# tic_tac_toe.net
KiCad netlist of a schematic drawn in EAGLE
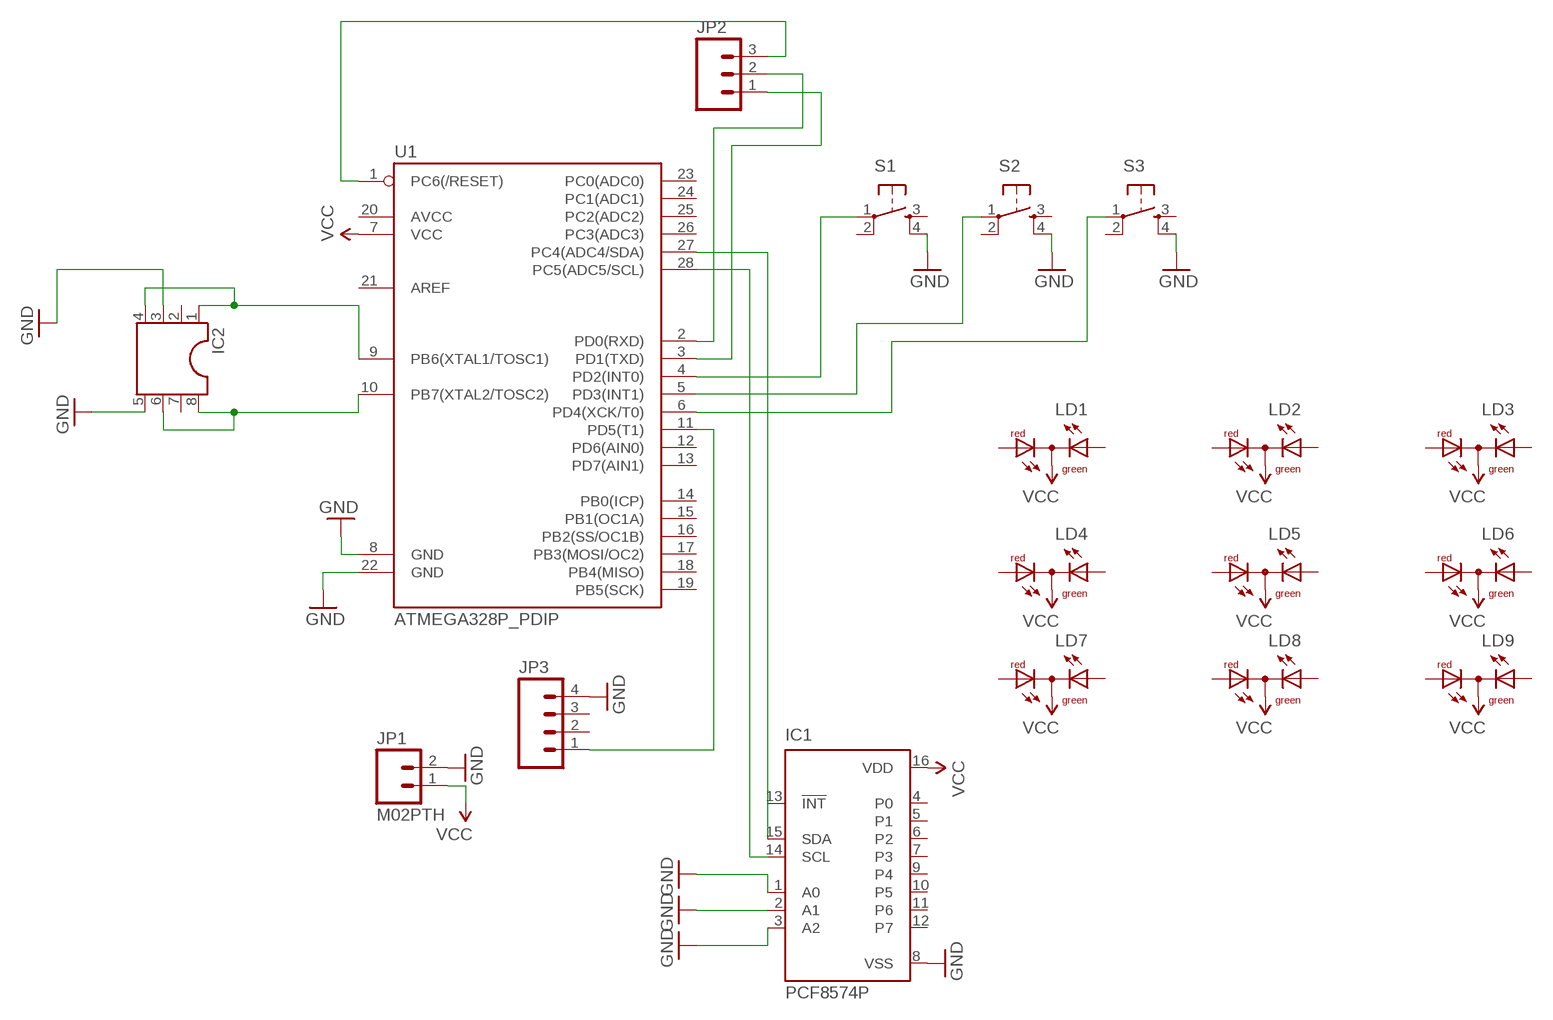
[diagram p0: schematic, sheet 1]

(export (version "E")
  (design (tool "Eeschema 10.0.6"))
  (components
    (comp (ref "IC1")
      (value "PCF8574P")
      (footprint "eagle-import:DIL16")
      (fields (field (name "MPN") "PCF8574PN"))
      (libsource (lib "eagle-import") (part "PCF8574P"))
    )
    (comp (ref "IC2")
      (value "DIL8S")
      (footprint "eagle-import:SOCKET-08")
      (libsource (lib "eagle-import") (part "DIL8S"))
    )
    (comp (ref "JP1")
      (value "M02PTH")
      (footprint "eagle-import:1X02")
      (libsource (lib "eagle-import") (part "M02PTH"))
    )
    (comp (ref "JP2")
      (value "M03PTH")
      (footprint "eagle-import:1X03")
      (libsource (lib "eagle-import") (part "M03PTH"))
    )
    (comp (ref "JP3")
      (value "M04PTH")
      (footprint "eagle-import:1X04")
      (libsource (lib "eagle-import") (part "M04PTH"))
    )
    (comp (ref "LD1")
      (value "DUOLED-RG-C")
      (footprint "eagle-import:DUOLED-C-5MM")
      (libsource (lib "eagle-import") (part "DUOLED-RG-C"))
    )
    (comp (ref "LD2")
      (value "DUOLED-RG-C")
      (footprint "eagle-import:DUOLED-C-5MM")
      (libsource (lib "eagle-import") (part "DUOLED-RG-C"))
    )
    (comp (ref "LD3")
      (value "DUOLED-RG-C")
      (footprint "eagle-import:DUOLED-C-5MM")
      (libsource (lib "eagle-import") (part "DUOLED-RG-C"))
    )
    (comp (ref "LD4")
      (value "DUOLED-RG-C")
      (footprint "eagle-import:DUOLED-C-5MM")
      (libsource (lib "eagle-import") (part "DUOLED-RG-C"))
    )
    (comp (ref "LD5")
      (value "DUOLED-RG-C")
      (footprint "eagle-import:DUOLED-C-5MM")
      (libsource (lib "eagle-import") (part "DUOLED-RG-C"))
    )
    (comp (ref "LD6")
      (value "DUOLED-RG-C")
      (footprint "eagle-import:DUOLED-C-5MM")
      (libsource (lib "eagle-import") (part "DUOLED-RG-C"))
    )
    (comp (ref "LD7")
      (value "DUOLED-RG-C")
      (footprint "eagle-import:DUOLED-C-5MM")
      (libsource (lib "eagle-import") (part "DUOLED-RG-C"))
    )
    (comp (ref "LD8")
      (value "DUOLED-RG-C")
      (footprint "eagle-import:DUOLED-C-5MM")
      (libsource (lib "eagle-import") (part "DUOLED-RG-C"))
    )
    (comp (ref "LD9")
      (value "DUOLED-RG-C")
      (footprint "eagle-import:DUOLED-C-5MM")
      (libsource (lib "eagle-import") (part "DUOLED-RG-C"))
    )
    (comp (ref "S1")
      (value "TAC_SWITCHPTH")
      (footprint "eagle-import:TACTILE-PTH")
      (libsource (lib "eagle-import") (part "TAC_SWITCHPTH"))
    )
    (comp (ref "S2")
      (value "TAC_SWITCHPTH")
      (footprint "eagle-import:TACTILE-PTH")
      (libsource (lib "eagle-import") (part "TAC_SWITCHPTH"))
    )
    (comp (ref "S3")
      (value "TAC_SWITCHPTH")
      (footprint "eagle-import:TACTILE-PTH")
      (libsource (lib "eagle-import") (part "TAC_SWITCHPTH"))
    )
    (comp (ref "U1")
      (value "ATMEGA328P_PDIP")
      (footprint "eagle-import:DIL28-3")
      (libsource (lib "eagle-import") (part "ATMEGA328P_PDIP"))
    )
  )
  (nets
    (net (code "1") (name "GND") (class "Default")
      (node (ref "IC1") (pin "1") (pinfunction "A0_1") (pintype "input"))
      (node (ref "IC1") (pin "2") (pinfunction "A1_2") (pintype "input"))
      (node (ref "IC1") (pin "3") (pinfunction "A2_3") (pintype "input"))
      (node (ref "IC1") (pin "8") (pinfunction "VSS_8") (pintype "power_in"))
      (node (ref "IC2") (pin "3") (pinfunction "3_3") (pintype "passive"))
      (node (ref "IC2") (pin "5") (pinfunction "5_5") (pintype "passive"))
      (node (ref "JP1") (pin "2") (pinfunction "2_2") (pintype "passive"))
      (node (ref "JP3") (pin "4") (pinfunction "4_4") (pintype "passive"))
      (node (ref "S1") (pin "4") (pinfunction "4_4") (pintype "passive"))
      (node (ref "S2") (pin "4") (pinfunction "4_4") (pintype "passive"))
      (node (ref "S3") (pin "4") (pinfunction "4_4") (pintype "passive"))
      (node (ref "U1") (pin "22") (pinfunction "GND_22") (pintype "bidirectional"))
      (node (ref "U1") (pin "8") (pinfunction "GND_8") (pintype "bidirectional"))
    )
    (net (code "2") (name "Net-(IC1-SCL)") (class "Default")
      (node (ref "IC1") (pin "14") (pinfunction "SCL_14") (pintype "input"))
      (node (ref "U1") (pin "28") (pinfunction "PC5(ADC5/SCL)_28") (pintype "bidirectional"))
    )
    (net (code "3") (name "Net-(IC1-SDA)") (class "Default")
      (node (ref "IC1") (pin "15") (pinfunction "SDA_15") (pintype "bidirectional"))
      (node (ref "U1") (pin "27") (pinfunction "PC4(ADC4/SDA)_27") (pintype "bidirectional"))
    )
    (net (code "4") (name "Net-(U1-PB6(XTAL1{slash}TOSC1))") (class "Default")
      (node (ref "IC2") (pin "1") (pinfunction "1_1") (pintype "passive"))
      (node (ref "IC2") (pin "4") (pinfunction "4_4") (pintype "passive"))
      (node (ref "U1") (pin "9") (pinfunction "PB6(XTAL1/TOSC1)_9") (pintype "bidirectional"))
    )
    (net (code "5") (name "Net-(U1-PB7(XTAL2{slash}TOSC2))") (class "Default")
      (node (ref "IC2") (pin "6") (pinfunction "6_6") (pintype "passive"))
      (node (ref "IC2") (pin "8") (pinfunction "8_8") (pintype "passive"))
      (node (ref "U1") (pin "10") (pinfunction "PB7(XTAL2/TOSC2)_10") (pintype "bidirectional"))
    )
    (net (code "6") (name "Net-(U1-PC6({slash}RESET))") (class "Default")
      (node (ref "JP2") (pin "3") (pinfunction "3_3") (pintype "passive"))
      (node (ref "U1") (pin "1") (pinfunction "PC6(/RESET)_1") (pintype "bidirectional"))
    )
    (net (code "7") (name "Net-(U1-PD0(RXD))") (class "Default")
      (node (ref "JP2") (pin "2") (pinfunction "2_2") (pintype "passive"))
      (node (ref "U1") (pin "2") (pinfunction "PD0(RXD)_2") (pintype "bidirectional"))
    )
    (net (code "8") (name "Net-(U1-PD1(TXD))") (class "Default")
      (node (ref "JP2") (pin "1") (pinfunction "1_1") (pintype "passive"))
      (node (ref "U1") (pin "3") (pinfunction "PD1(TXD)_3") (pintype "bidirectional"))
    )
    (net (code "9") (name "Net-(U1-PD2(INT0))") (class "Default")
      (node (ref "S1") (pin "1") (pinfunction "1_1") (pintype "passive"))
      (node (ref "U1") (pin "4") (pinfunction "PD2(INT0)_4") (pintype "bidirectional"))
    )
    (net (code "10") (name "Net-(U1-PD3(INT1))") (class "Default")
      (node (ref "S2") (pin "1") (pinfunction "1_1") (pintype "passive"))
      (node (ref "U1") (pin "5") (pinfunction "PD3(INT1)_5") (pintype "bidirectional"))
    )
    (net (code "11") (name "Net-(U1-PD4(XCK{slash}T0))") (class "Default")
      (node (ref "S3") (pin "1") (pinfunction "1_1") (pintype "passive"))
      (node (ref "U1") (pin "6") (pinfunction "PD4(XCK/T0)_6") (pintype "bidirectional"))
    )
    (net (code "12") (name "Net-(U1-PD5(T1))") (class "Default")
      (node (ref "JP3") (pin "1") (pinfunction "1_1") (pintype "passive"))
      (node (ref "U1") (pin "11") (pinfunction "PD5(T1)_11") (pintype "bidirectional"))
    )
    (net (code "13") (name "VCC") (class "Default")
      (node (ref "IC1") (pin "16") (pinfunction "VDD_16") (pintype "power_in"))
      (node (ref "JP1") (pin "1") (pinfunction "1_1") (pintype "passive"))
      (node (ref "LD1") (pin "C") (pinfunction "C_C") (pintype "passive"))
      (node (ref "LD2") (pin "C") (pinfunction "C_C") (pintype "passive"))
      (node (ref "LD3") (pin "C") (pinfunction "C_C") (pintype "passive"))
      (node (ref "LD4") (pin "C") (pinfunction "C_C") (pintype "passive"))
      (node (ref "LD5") (pin "C") (pinfunction "C_C") (pintype "passive"))
      (node (ref "LD6") (pin "C") (pinfunction "C_C") (pintype "passive"))
      (node (ref "LD7") (pin "C") (pinfunction "C_C") (pintype "passive"))
      (node (ref "LD8") (pin "C") (pinfunction "C_C") (pintype "passive"))
      (node (ref "LD9") (pin "C") (pinfunction "C_C") (pintype "passive"))
      (node (ref "U1") (pin "7") (pinfunction "VCC_7") (pintype "bidirectional"))
    )
    (net (code "14") (name "unconnected-(IC1-P0-Pad4)") (class "Default")
      (node (ref "IC1") (pin "4") (pinfunction "P0_4") (pintype "bidirectional"))
    )
    (net (code "15") (name "unconnected-(IC1-P1-Pad5)") (class "Default")
      (node (ref "IC1") (pin "5") (pinfunction "P1_5") (pintype "bidirectional"))
    )
    (net (code "16") (name "unconnected-(IC1-P2-Pad6)") (class "Default")
      (node (ref "IC1") (pin "6") (pinfunction "P2_6") (pintype "bidirectional"))
    )
    (net (code "17") (name "unconnected-(IC1-P3-Pad7)") (class "Default")
      (node (ref "IC1") (pin "7") (pinfunction "P3_7") (pintype "bidirectional"))
    )
    (net (code "18") (name "unconnected-(IC1-P4-Pad9)") (class "Default")
      (node (ref "IC1") (pin "9") (pinfunction "P4_9") (pintype "bidirectional"))
    )
    (net (code "19") (name "unconnected-(IC1-P5-Pad10)") (class "Default")
      (node (ref "IC1") (pin "10") (pinfunction "P5_10") (pintype "bidirectional"))
    )
    (net (code "20") (name "unconnected-(IC1-P6-Pad11)") (class "Default")
      (node (ref "IC1") (pin "11") (pinfunction "P6_11") (pintype "bidirectional"))
    )
    (net (code "21") (name "unconnected-(IC1-P7-Pad12)") (class "Default")
      (node (ref "IC1") (pin "12") (pinfunction "P7_12") (pintype "bidirectional"))
    )
    (net (code "22") (name "unconnected-(IC1-~{INT}-Pad13)") (class "Default")
      (node (ref "IC1") (pin "13") (pinfunction "~{INT}_13") (pintype "output"))
    )
    (net (code "23") (name "unconnected-(IC2-Pad2)") (class "Default")
      (node (ref "IC2") (pin "2") (pinfunction "2_2") (pintype "passive"))
    )
    (net (code "24") (name "unconnected-(IC2-Pad7)") (class "Default")
      (node (ref "IC2") (pin "7") (pinfunction "7_7") (pintype "passive"))
    )
    (net (code "25") (name "unconnected-(JP3-Pad2)") (class "Default")
      (node (ref "JP3") (pin "2") (pinfunction "2_2") (pintype "passive"))
    )
    (net (code "26") (name "unconnected-(JP3-Pad3)") (class "Default")
      (node (ref "JP3") (pin "3") (pinfunction "3_3") (pintype "passive"))
    )
    (net (code "27") (name "unconnected-(LD1-AG-PadAX)") (class "Default")
      (node (ref "LD1") (pin "AX") (pinfunction "AG_AX") (pintype "passive"))
    )
    (net (code "28") (name "unconnected-(LD1-PadAR)") (class "Default")
      (node (ref "LD1") (pin "AR") (pinfunction "AR_AR") (pintype "passive"))
    )
    (net (code "29") (name "unconnected-(LD2-AG-PadAX)") (class "Default")
      (node (ref "LD2") (pin "AX") (pinfunction "AG_AX") (pintype "passive"))
    )
    (net (code "30") (name "unconnected-(LD2-PadAR)") (class "Default")
      (node (ref "LD2") (pin "AR") (pinfunction "AR_AR") (pintype "passive"))
    )
    (net (code "31") (name "unconnected-(LD3-AG-PadAX)") (class "Default")
      (node (ref "LD3") (pin "AX") (pinfunction "AG_AX") (pintype "passive"))
    )
    (net (code "32") (name "unconnected-(LD3-PadAR)") (class "Default")
      (node (ref "LD3") (pin "AR") (pinfunction "AR_AR") (pintype "passive"))
    )
    (net (code "33") (name "unconnected-(LD4-AG-PadAX)") (class "Default")
      (node (ref "LD4") (pin "AX") (pinfunction "AG_AX") (pintype "passive"))
    )
    (net (code "34") (name "unconnected-(LD4-PadAR)") (class "Default")
      (node (ref "LD4") (pin "AR") (pinfunction "AR_AR") (pintype "passive"))
    )
    (net (code "35") (name "unconnected-(LD5-AG-PadAX)") (class "Default")
      (node (ref "LD5") (pin "AX") (pinfunction "AG_AX") (pintype "passive"))
    )
    (net (code "36") (name "unconnected-(LD5-PadAR)") (class "Default")
      (node (ref "LD5") (pin "AR") (pinfunction "AR_AR") (pintype "passive"))
    )
    (net (code "37") (name "unconnected-(LD6-AG-PadAX)") (class "Default")
      (node (ref "LD6") (pin "AX") (pinfunction "AG_AX") (pintype "passive"))
    )
    (net (code "38") (name "unconnected-(LD6-PadAR)") (class "Default")
      (node (ref "LD6") (pin "AR") (pinfunction "AR_AR") (pintype "passive"))
    )
    (net (code "39") (name "unconnected-(LD7-AG-PadAX)") (class "Default")
      (node (ref "LD7") (pin "AX") (pinfunction "AG_AX") (pintype "passive"))
    )
    (net (code "40") (name "unconnected-(LD7-PadAR)") (class "Default")
      (node (ref "LD7") (pin "AR") (pinfunction "AR_AR") (pintype "passive"))
    )
    (net (code "41") (name "unconnected-(LD8-AG-PadAX)") (class "Default")
      (node (ref "LD8") (pin "AX") (pinfunction "AG_AX") (pintype "passive"))
    )
    (net (code "42") (name "unconnected-(LD8-PadAR)") (class "Default")
      (node (ref "LD8") (pin "AR") (pinfunction "AR_AR") (pintype "passive"))
    )
    (net (code "43") (name "unconnected-(LD9-AG-PadAX)") (class "Default")
      (node (ref "LD9") (pin "AX") (pinfunction "AG_AX") (pintype "passive"))
    )
    (net (code "44") (name "unconnected-(LD9-PadAR)") (class "Default")
      (node (ref "LD9") (pin "AR") (pinfunction "AR_AR") (pintype "passive"))
    )
    (net (code "45") (name "unconnected-(S1-Pad2)") (class "Default")
      (node (ref "S1") (pin "2") (pinfunction "2_2") (pintype "passive"))
    )
    (net (code "46") (name "unconnected-(S1-Pad3)") (class "Default")
      (node (ref "S1") (pin "3") (pinfunction "3_3") (pintype "passive"))
    )
    (net (code "47") (name "unconnected-(S2-Pad2)") (class "Default")
      (node (ref "S2") (pin "2") (pinfunction "2_2") (pintype "passive"))
    )
    (net (code "48") (name "unconnected-(S2-Pad3)") (class "Default")
      (node (ref "S2") (pin "3") (pinfunction "3_3") (pintype "passive"))
    )
    (net (code "49") (name "unconnected-(S3-Pad2)") (class "Default")
      (node (ref "S3") (pin "2") (pinfunction "2_2") (pintype "passive"))
    )
    (net (code "50") (name "unconnected-(S3-Pad3)") (class "Default")
      (node (ref "S3") (pin "3") (pinfunction "3_3") (pintype "passive"))
    )
    (net (code "51") (name "unconnected-(U1-AREF-Pad21)") (class "Default")
      (node (ref "U1") (pin "21") (pinfunction "AREF_21") (pintype "bidirectional"))
    )
    (net (code "52") (name "unconnected-(U1-AVCC-Pad20)") (class "Default")
      (node (ref "U1") (pin "20") (pinfunction "AVCC_20") (pintype "bidirectional"))
    )
    (net (code "53") (name "unconnected-(U1-PB0(ICP)-Pad14)") (class "Default")
      (node (ref "U1") (pin "14") (pinfunction "PB0(ICP)_14") (pintype "bidirectional"))
    )
    (net (code "54") (name "unconnected-(U1-PB1(OC1A)-Pad15)") (class "Default")
      (node (ref "U1") (pin "15") (pinfunction "PB1(OC1A)_15") (pintype "bidirectional"))
    )
    (net (code "55") (name "unconnected-(U1-PB2(SS{slash}OC1B)-Pad16)") (class "Default")
      (node (ref "U1") (pin "16") (pinfunction "PB2(SS/OC1B)_16") (pintype "bidirectional"))
    )
    (net (code "56") (name "unconnected-(U1-PB3(MOSI{slash}OC2)-Pad17)") (class "Default")
      (node (ref "U1") (pin "17") (pinfunction "PB3(MOSI/OC2)_17") (pintype "bidirectional"))
    )
    (net (code "57") (name "unconnected-(U1-PB4(MISO)-Pad18)") (class "Default")
      (node (ref "U1") (pin "18") (pinfunction "PB4(MISO)_18") (pintype "bidirectional"))
    )
    (net (code "58") (name "unconnected-(U1-PB5(SCK)-Pad19)") (class "Default")
      (node (ref "U1") (pin "19") (pinfunction "PB5(SCK)_19") (pintype "bidirectional"))
    )
    (net (code "59") (name "unconnected-(U1-PC0(ADC0)-Pad23)") (class "Default")
      (node (ref "U1") (pin "23") (pinfunction "PC0(ADC0)_23") (pintype "bidirectional"))
    )
    (net (code "60") (name "unconnected-(U1-PC1(ADC1)-Pad24)") (class "Default")
      (node (ref "U1") (pin "24") (pinfunction "PC1(ADC1)_24") (pintype "bidirectional"))
    )
    (net (code "61") (name "unconnected-(U1-PC2(ADC2)-Pad25)") (class "Default")
      (node (ref "U1") (pin "25") (pinfunction "PC2(ADC2)_25") (pintype "bidirectional"))
    )
    (net (code "62") (name "unconnected-(U1-PC3(ADC3)-Pad26)") (class "Default")
      (node (ref "U1") (pin "26") (pinfunction "PC3(ADC3)_26") (pintype "bidirectional"))
    )
    (net (code "63") (name "unconnected-(U1-PD6(AIN0)-Pad12)") (class "Default")
      (node (ref "U1") (pin "12") (pinfunction "PD6(AIN0)_12") (pintype "bidirectional"))
    )
    (net (code "64") (name "unconnected-(U1-PD7(AIN1)-Pad13)") (class "Default")
      (node (ref "U1") (pin "13") (pinfunction "PD7(AIN1)_13") (pintype "bidirectional"))
    )
  )
)
